# FuzzOfWar.net
KiCad netlist of a schematic drawn in EAGLE
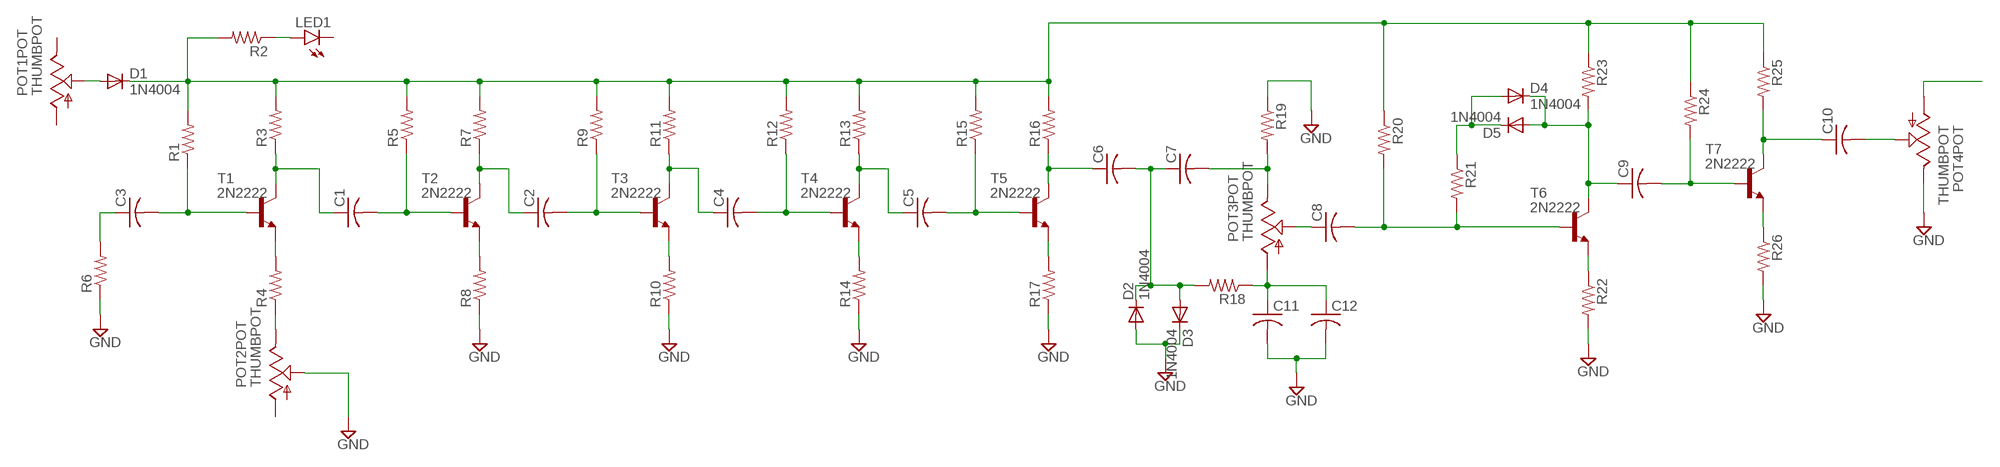
[diagram p0: schematic, sheet 1]

(export (version "E")
  (design (tool "Eeschema 10.0.6"))
  (components
    (comp (ref "C1")
      (value "C-USC0603")
      (footprint "eagle-import:C0603")
      (libsource (lib "eagle-import") (part "C-USC0603"))
    )
    (comp (ref "C2")
      (value "C-USC0603")
      (footprint "eagle-import:C0603")
      (libsource (lib "eagle-import") (part "C-USC0603"))
    )
    (comp (ref "C3")
      (value "C-USC0603")
      (footprint "eagle-import:C0603")
      (libsource (lib "eagle-import") (part "C-USC0603"))
    )
    (comp (ref "C4")
      (value "C-USC0603")
      (footprint "eagle-import:C0603")
      (libsource (lib "eagle-import") (part "C-USC0603"))
    )
    (comp (ref "C5")
      (value "C-USC0603")
      (footprint "eagle-import:C0603")
      (libsource (lib "eagle-import") (part "C-USC0603"))
    )
    (comp (ref "C6")
      (value "C-USC0603")
      (footprint "eagle-import:C0603")
      (libsource (lib "eagle-import") (part "C-USC0603"))
    )
    (comp (ref "C7")
      (value "C-USC0603")
      (footprint "eagle-import:C0603")
      (libsource (lib "eagle-import") (part "C-USC0603"))
    )
    (comp (ref "C8")
      (value "C-USC0603")
      (footprint "eagle-import:C0603")
      (libsource (lib "eagle-import") (part "C-USC0603"))
    )
    (comp (ref "C9")
      (value "C-USC0603")
      (footprint "eagle-import:C0603")
      (libsource (lib "eagle-import") (part "C-USC0603"))
    )
    (comp (ref "C10")
      (value "C-USC0603")
      (footprint "eagle-import:C0603")
      (libsource (lib "eagle-import") (part "C-USC0603"))
    )
    (comp (ref "C11")
      (value "C-USC0603")
      (footprint "eagle-import:C0603")
      (libsource (lib "eagle-import") (part "C-USC0603"))
    )
    (comp (ref "C12")
      (value "C-USC0603")
      (footprint "eagle-import:C0603")
      (libsource (lib "eagle-import") (part "C-USC0603"))
    )
    (comp (ref "D1")
      (value "1N4004")
      (footprint "eagle-import:DO41-10")
      (libsource (lib "eagle-import") (part "1N4004"))
    )
    (comp (ref "D2")
      (value "1N4004")
      (footprint "eagle-import:DO41-10")
      (libsource (lib "eagle-import") (part "1N4004"))
    )
    (comp (ref "D3")
      (value "1N4004")
      (footprint "eagle-import:DO41-10")
      (libsource (lib "eagle-import") (part "1N4004"))
    )
    (comp (ref "D4")
      (value "1N4004")
      (footprint "eagle-import:DO41-10")
      (libsource (lib "eagle-import") (part "1N4004"))
    )
    (comp (ref "D5")
      (value "1N4004")
      (footprint "eagle-import:DO41-10")
      (libsource (lib "eagle-import") (part "1N4004"))
    )
    (comp (ref "LED1")
      (value "LED3MM")
      (footprint "eagle-import:LED3MM")
      (libsource (lib "eagle-import") (part "LED3MM"))
    )
    (comp (ref "POT1")
      (value "THUMBPOT")
      (footprint "eagle-import:THUMBWHEEL")
      (libsource (lib "eagle-import") (part "THUMBPOT"))
    )
    (comp (ref "POT2")
      (value "THUMBPOT")
      (footprint "eagle-import:THUMBWHEEL")
      (libsource (lib "eagle-import") (part "THUMBPOT"))
    )
    (comp (ref "POT3")
      (value "THUMBPOT")
      (footprint "eagle-import:THUMBWHEEL")
      (libsource (lib "eagle-import") (part "THUMBPOT"))
    )
    (comp (ref "POT4")
      (value "THUMBPOT")
      (footprint "eagle-import:THUMBWHEEL")
      (libsource (lib "eagle-import") (part "THUMBPOT"))
    )
    (comp (ref "R1")
      (value "R-US_R0603")
      (footprint "eagle-import:R0603")
      (libsource (lib "eagle-import") (part "R-US_R0603"))
    )
    (comp (ref "R2")
      (value "R-US_R0603")
      (footprint "eagle-import:R0603")
      (libsource (lib "eagle-import") (part "R-US_R0603"))
    )
    (comp (ref "R3")
      (value "R-US_R0603")
      (footprint "eagle-import:R0603")
      (libsource (lib "eagle-import") (part "R-US_R0603"))
    )
    (comp (ref "R4")
      (value "R-US_R0603")
      (footprint "eagle-import:R0603")
      (libsource (lib "eagle-import") (part "R-US_R0603"))
    )
    (comp (ref "R5")
      (value "R-US_R0603")
      (footprint "eagle-import:R0603")
      (libsource (lib "eagle-import") (part "R-US_R0603"))
    )
    (comp (ref "R6")
      (value "R-US_R0603")
      (footprint "eagle-import:R0603")
      (libsource (lib "eagle-import") (part "R-US_R0603"))
    )
    (comp (ref "R7")
      (value "R-US_R0603")
      (footprint "eagle-import:R0603")
      (libsource (lib "eagle-import") (part "R-US_R0603"))
    )
    (comp (ref "R8")
      (value "R-US_R0603")
      (footprint "eagle-import:R0603")
      (libsource (lib "eagle-import") (part "R-US_R0603"))
    )
    (comp (ref "R9")
      (value "R-US_R0603")
      (footprint "eagle-import:R0603")
      (libsource (lib "eagle-import") (part "R-US_R0603"))
    )
    (comp (ref "R10")
      (value "R-US_R0603")
      (footprint "eagle-import:R0603")
      (libsource (lib "eagle-import") (part "R-US_R0603"))
    )
    (comp (ref "R11")
      (value "R-US_R0603")
      (footprint "eagle-import:R0603")
      (libsource (lib "eagle-import") (part "R-US_R0603"))
    )
    (comp (ref "R12")
      (value "R-US_R0603")
      (footprint "eagle-import:R0603")
      (libsource (lib "eagle-import") (part "R-US_R0603"))
    )
    (comp (ref "R13")
      (value "R-US_R0603")
      (footprint "eagle-import:R0603")
      (libsource (lib "eagle-import") (part "R-US_R0603"))
    )
    (comp (ref "R14")
      (value "R-US_R0603")
      (footprint "eagle-import:R0603")
      (libsource (lib "eagle-import") (part "R-US_R0603"))
    )
    (comp (ref "R15")
      (value "R-US_R0603")
      (footprint "eagle-import:R0603")
      (libsource (lib "eagle-import") (part "R-US_R0603"))
    )
    (comp (ref "R16")
      (value "R-US_R0603")
      (footprint "eagle-import:R0603")
      (libsource (lib "eagle-import") (part "R-US_R0603"))
    )
    (comp (ref "R17")
      (value "R-US_R0603")
      (footprint "eagle-import:R0603")
      (libsource (lib "eagle-import") (part "R-US_R0603"))
    )
    (comp (ref "R18")
      (value "R-US_R0603")
      (footprint "eagle-import:R0603")
      (libsource (lib "eagle-import") (part "R-US_R0603"))
    )
    (comp (ref "R19")
      (value "R-US_R0603")
      (footprint "eagle-import:R0603")
      (libsource (lib "eagle-import") (part "R-US_R0603"))
    )
    (comp (ref "R20")
      (value "R-US_R0603")
      (footprint "eagle-import:R0603")
      (libsource (lib "eagle-import") (part "R-US_R0603"))
    )
    (comp (ref "R21")
      (value "R-US_R0603")
      (footprint "eagle-import:R0603")
      (libsource (lib "eagle-import") (part "R-US_R0603"))
    )
    (comp (ref "R22")
      (value "R-US_R0603")
      (footprint "eagle-import:R0603")
      (libsource (lib "eagle-import") (part "R-US_R0603"))
    )
    (comp (ref "R23")
      (value "R-US_R0603")
      (footprint "eagle-import:R0603")
      (libsource (lib "eagle-import") (part "R-US_R0603"))
    )
    (comp (ref "R24")
      (value "R-US_R0603")
      (footprint "eagle-import:R0603")
      (libsource (lib "eagle-import") (part "R-US_R0603"))
    )
    (comp (ref "R25")
      (value "R-US_R0603")
      (footprint "eagle-import:R0603")
      (libsource (lib "eagle-import") (part "R-US_R0603"))
    )
    (comp (ref "R26")
      (value "R-US_R0603")
      (footprint "eagle-import:R0603")
      (libsource (lib "eagle-import") (part "R-US_R0603"))
    )
    (comp (ref "T1")
      (value "2N2222")
      (footprint "eagle-import:TO92-EBC-OVAL")
      (libsource (lib "eagle-import") (part "2N2222"))
    )
    (comp (ref "T2")
      (value "2N2222")
      (footprint "eagle-import:TO92-EBC-OVAL")
      (libsource (lib "eagle-import") (part "2N2222"))
    )
    (comp (ref "T3")
      (value "2N2222")
      (footprint "eagle-import:TO92-EBC-OVAL")
      (libsource (lib "eagle-import") (part "2N2222"))
    )
    (comp (ref "T4")
      (value "2N2222")
      (footprint "eagle-import:TO92-EBC-OVAL")
      (libsource (lib "eagle-import") (part "2N2222"))
    )
    (comp (ref "T5")
      (value "2N2222")
      (footprint "eagle-import:TO92-EBC-OVAL")
      (libsource (lib "eagle-import") (part "2N2222"))
    )
    (comp (ref "T6")
      (value "2N2222")
      (footprint "eagle-import:TO92-EBC-OVAL")
      (libsource (lib "eagle-import") (part "2N2222"))
    )
    (comp (ref "T7")
      (value "2N2222")
      (footprint "eagle-import:TO92-EBC-OVAL")
      (libsource (lib "eagle-import") (part "2N2222"))
    )
  )
  (nets
    (net (code "1") (name "GND") (class "Default")
      (node (ref "C11") (pin "2") (pinfunction "2_2") (pintype "passive"))
      (node (ref "C12") (pin "2") (pinfunction "2_2") (pintype "passive"))
      (node (ref "D2") (pin "A") (pinfunction "A_A") (pintype "passive"))
      (node (ref "D3") (pin "C") (pinfunction "C_C") (pintype "passive"))
      (node (ref "POT2") (pin "2") (pinfunction "S_2") (pintype "passive"))
      (node (ref "POT4") (pin "3") (pinfunction "E_3") (pintype "passive"))
      (node (ref "R10") (pin "1") (pinfunction "1_1") (pintype "passive"))
      (node (ref "R14") (pin "1") (pinfunction "1_1") (pintype "passive"))
      (node (ref "R17") (pin "1") (pinfunction "1_1") (pintype "passive"))
      (node (ref "R19") (pin "1") (pinfunction "1_1") (pintype "passive"))
      (node (ref "R22") (pin "2") (pinfunction "2_2") (pintype "passive"))
      (node (ref "R26") (pin "2") (pinfunction "2_2") (pintype "passive"))
      (node (ref "R6") (pin "1") (pinfunction "1_1") (pintype "passive"))
      (node (ref "R8") (pin "1") (pinfunction "1_1") (pintype "passive"))
    )
    (net (code "2") (name "Net-(C1-Pad1)") (class "Default")
      (node (ref "C1") (pin "1") (pinfunction "1_1") (pintype "passive"))
      (node (ref "R3") (pin "1") (pinfunction "1_1") (pintype "passive"))
      (node (ref "T1") (pin "C") (pinfunction "C_C") (pintype "passive"))
    )
    (net (code "3") (name "Net-(C1-Pad2)") (class "Default")
      (node (ref "C1") (pin "2") (pinfunction "2_2") (pintype "passive"))
      (node (ref "R5") (pin "1") (pinfunction "1_1") (pintype "passive"))
      (node (ref "T2") (pin "B") (pinfunction "B_B") (pintype "passive"))
    )
    (net (code "4") (name "Net-(C2-Pad1)") (class "Default")
      (node (ref "C2") (pin "1") (pinfunction "1_1") (pintype "passive"))
      (node (ref "R7") (pin "1") (pinfunction "1_1") (pintype "passive"))
      (node (ref "T2") (pin "C") (pinfunction "C_C") (pintype "passive"))
    )
    (net (code "5") (name "Net-(C2-Pad2)") (class "Default")
      (node (ref "C2") (pin "2") (pinfunction "2_2") (pintype "passive"))
      (node (ref "R9") (pin "1") (pinfunction "1_1") (pintype "passive"))
      (node (ref "T3") (pin "B") (pinfunction "B_B") (pintype "passive"))
    )
    (net (code "6") (name "Net-(C3-Pad1)") (class "Default")
      (node (ref "C3") (pin "1") (pinfunction "1_1") (pintype "passive"))
      (node (ref "R6") (pin "2") (pinfunction "2_2") (pintype "passive"))
    )
    (net (code "7") (name "Net-(C3-Pad2)") (class "Default")
      (node (ref "C3") (pin "2") (pinfunction "2_2") (pintype "passive"))
      (node (ref "R1") (pin "1") (pinfunction "1_1") (pintype "passive"))
      (node (ref "T1") (pin "B") (pinfunction "B_B") (pintype "passive"))
    )
    (net (code "8") (name "Net-(C4-Pad1)") (class "Default")
      (node (ref "C4") (pin "1") (pinfunction "1_1") (pintype "passive"))
      (node (ref "R11") (pin "1") (pinfunction "1_1") (pintype "passive"))
      (node (ref "T3") (pin "C") (pinfunction "C_C") (pintype "passive"))
    )
    (net (code "9") (name "Net-(C4-Pad2)") (class "Default")
      (node (ref "C4") (pin "2") (pinfunction "2_2") (pintype "passive"))
      (node (ref "R12") (pin "1") (pinfunction "1_1") (pintype "passive"))
      (node (ref "T4") (pin "B") (pinfunction "B_B") (pintype "passive"))
    )
    (net (code "10") (name "Net-(C5-Pad1)") (class "Default")
      (node (ref "C5") (pin "1") (pinfunction "1_1") (pintype "passive"))
      (node (ref "R13") (pin "1") (pinfunction "1_1") (pintype "passive"))
      (node (ref "T4") (pin "C") (pinfunction "C_C") (pintype "passive"))
    )
    (net (code "11") (name "Net-(C5-Pad2)") (class "Default")
      (node (ref "C5") (pin "2") (pinfunction "2_2") (pintype "passive"))
      (node (ref "R15") (pin "1") (pinfunction "1_1") (pintype "passive"))
      (node (ref "T5") (pin "B") (pinfunction "B_B") (pintype "passive"))
    )
    (net (code "12") (name "Net-(C6-Pad1)") (class "Default")
      (node (ref "C6") (pin "1") (pinfunction "1_1") (pintype "passive"))
      (node (ref "R16") (pin "1") (pinfunction "1_1") (pintype "passive"))
      (node (ref "T5") (pin "C") (pinfunction "C_C") (pintype "passive"))
    )
    (net (code "13") (name "Net-(C6-Pad2)") (class "Default")
      (node (ref "C6") (pin "2") (pinfunction "2_2") (pintype "passive"))
      (node (ref "C7") (pin "1") (pinfunction "1_1") (pintype "passive"))
      (node (ref "D2") (pin "C") (pinfunction "C_C") (pintype "passive"))
      (node (ref "D3") (pin "A") (pinfunction "A_A") (pintype "passive"))
      (node (ref "R18") (pin "2") (pinfunction "2_2") (pintype "passive"))
    )
    (net (code "14") (name "Net-(C8-Pad2)") (class "Default")
      (node (ref "C8") (pin "2") (pinfunction "2_2") (pintype "passive"))
      (node (ref "R20") (pin "2") (pinfunction "2_2") (pintype "passive"))
      (node (ref "R21") (pin "2") (pinfunction "2_2") (pintype "passive"))
      (node (ref "T6") (pin "B") (pinfunction "B_B") (pintype "passive"))
    )
    (net (code "15") (name "Net-(C9-Pad1)") (class "Default")
      (node (ref "C9") (pin "1") (pinfunction "1_1") (pintype "passive"))
      (node (ref "D4") (pin "C") (pinfunction "C_C") (pintype "passive"))
      (node (ref "D5") (pin "A") (pinfunction "A_A") (pintype "passive"))
      (node (ref "R23") (pin "2") (pinfunction "2_2") (pintype "passive"))
      (node (ref "T6") (pin "C") (pinfunction "C_C") (pintype "passive"))
    )
    (net (code "16") (name "Net-(C9-Pad2)") (class "Default")
      (node (ref "C9") (pin "2") (pinfunction "2_2") (pintype "passive"))
      (node (ref "R24") (pin "2") (pinfunction "2_2") (pintype "passive"))
      (node (ref "T7") (pin "B") (pinfunction "B_B") (pintype "passive"))
    )
    (net (code "17") (name "Net-(C10-Pad1)") (class "Default")
      (node (ref "C10") (pin "1") (pinfunction "1_1") (pintype "passive"))
      (node (ref "R25") (pin "2") (pinfunction "2_2") (pintype "passive"))
      (node (ref "T7") (pin "C") (pinfunction "C_C") (pintype "passive"))
    )
    (net (code "18") (name "Net-(D1-PadC)") (class "Default")
      (node (ref "D1") (pin "C") (pinfunction "C_C") (pintype "passive"))
      (node (ref "R1") (pin "2") (pinfunction "2_2") (pintype "passive"))
      (node (ref "R11") (pin "2") (pinfunction "2_2") (pintype "passive"))
      (node (ref "R12") (pin "2") (pinfunction "2_2") (pintype "passive"))
      (node (ref "R13") (pin "2") (pinfunction "2_2") (pintype "passive"))
      (node (ref "R15") (pin "2") (pinfunction "2_2") (pintype "passive"))
      (node (ref "R16") (pin "2") (pinfunction "2_2") (pintype "passive"))
      (node (ref "R2") (pin "2") (pinfunction "2_2") (pintype "passive"))
      (node (ref "R20") (pin "1") (pinfunction "1_1") (pintype "passive"))
      (node (ref "R23") (pin "1") (pinfunction "1_1") (pintype "passive"))
      (node (ref "R24") (pin "1") (pinfunction "1_1") (pintype "passive"))
      (node (ref "R25") (pin "1") (pinfunction "1_1") (pintype "passive"))
      (node (ref "R3") (pin "2") (pinfunction "2_2") (pintype "passive"))
      (node (ref "R5") (pin "2") (pinfunction "2_2") (pintype "passive"))
      (node (ref "R7") (pin "2") (pinfunction "2_2") (pintype "passive"))
      (node (ref "R9") (pin "2") (pinfunction "2_2") (pintype "passive"))
    )
    (net (code "19") (name "Net-(D4-PadA)") (class "Default")
      (node (ref "D4") (pin "A") (pinfunction "A_A") (pintype "passive"))
      (node (ref "D5") (pin "C") (pinfunction "C_C") (pintype "passive"))
      (node (ref "R21") (pin "1") (pinfunction "1_1") (pintype "passive"))
    )
    (net (code "20") (name "Net-(LED1-PadA)") (class "Default")
      (node (ref "LED1") (pin "A") (pinfunction "A_A") (pintype "passive"))
      (node (ref "R2") (pin "1") (pinfunction "1_1") (pintype "passive"))
    )
    (net (code "21") (name "Net-(POT1A-S)") (class "Default")
      (node (ref "D1") (pin "A") (pinfunction "A_A") (pintype "passive"))
      (node (ref "POT1") (pin "2") (pinfunction "S_2") (pintype "passive"))
    )
    (net (code "22") (name "Net-(POT2A-E)") (class "Default")
      (node (ref "POT2") (pin "3") (pinfunction "E_3") (pintype "passive"))
      (node (ref "R4") (pin "1") (pinfunction "1_1") (pintype "passive"))
    )
    (net (code "23") (name "Net-(POT3A-A)") (class "Default")
      (node (ref "C11") (pin "1") (pinfunction "1_1") (pintype "passive"))
      (node (ref "C12") (pin "1") (pinfunction "1_1") (pintype "passive"))
      (node (ref "POT3") (pin "1") (pinfunction "A_1") (pintype "passive"))
      (node (ref "R18") (pin "1") (pinfunction "1_1") (pintype "passive"))
    )
    (net (code "24") (name "Net-(POT3A-E)") (class "Default")
      (node (ref "C7") (pin "2") (pinfunction "2_2") (pintype "passive"))
      (node (ref "POT3") (pin "3") (pinfunction "E_3") (pintype "passive"))
      (node (ref "R19") (pin "2") (pinfunction "2_2") (pintype "passive"))
    )
    (net (code "25") (name "Net-(POT3A-S)") (class "Default")
      (node (ref "C8") (pin "1") (pinfunction "1_1") (pintype "passive"))
      (node (ref "POT3") (pin "2") (pinfunction "S_2") (pintype "passive"))
    )
    (net (code "26") (name "Net-(POT4A-S)") (class "Default")
      (node (ref "C10") (pin "2") (pinfunction "2_2") (pintype "passive"))
      (node (ref "POT4") (pin "2") (pinfunction "S_2") (pintype "passive"))
    )
    (net (code "27") (name "Net-(R4-Pad2)") (class "Default")
      (node (ref "R4") (pin "2") (pinfunction "2_2") (pintype "passive"))
      (node (ref "T1") (pin "E") (pinfunction "E_E") (pintype "passive"))
    )
    (net (code "28") (name "Net-(R8-Pad2)") (class "Default")
      (node (ref "R8") (pin "2") (pinfunction "2_2") (pintype "passive"))
      (node (ref "T2") (pin "E") (pinfunction "E_E") (pintype "passive"))
    )
    (net (code "29") (name "Net-(R10-Pad2)") (class "Default")
      (node (ref "R10") (pin "2") (pinfunction "2_2") (pintype "passive"))
      (node (ref "T3") (pin "E") (pinfunction "E_E") (pintype "passive"))
    )
    (net (code "30") (name "Net-(R14-Pad2)") (class "Default")
      (node (ref "R14") (pin "2") (pinfunction "2_2") (pintype "passive"))
      (node (ref "T4") (pin "E") (pinfunction "E_E") (pintype "passive"))
    )
    (net (code "31") (name "Net-(R17-Pad2)") (class "Default")
      (node (ref "R17") (pin "2") (pinfunction "2_2") (pintype "passive"))
      (node (ref "T5") (pin "E") (pinfunction "E_E") (pintype "passive"))
    )
    (net (code "32") (name "Net-(R22-Pad1)") (class "Default")
      (node (ref "R22") (pin "1") (pinfunction "1_1") (pintype "passive"))
      (node (ref "T6") (pin "E") (pinfunction "E_E") (pintype "passive"))
    )
    (net (code "33") (name "Net-(R26-Pad1)") (class "Default")
      (node (ref "R26") (pin "1") (pinfunction "1_1") (pintype "passive"))
      (node (ref "T7") (pin "E") (pinfunction "E_E") (pintype "passive"))
    )
    (net (code "34") (name "unconnected-(LED1-C-PadK)") (class "Default")
      (node (ref "LED1") (pin "K") (pinfunction "C_K") (pintype "passive"))
    )
    (net (code "35") (name "unconnected-(POT1A-A-Pad1)") (class "Default")
      (node (ref "POT1") (pin "1") (pinfunction "A_1") (pintype "passive"))
    )
    (net (code "36") (name "unconnected-(POT1A-E-Pad3)") (class "Default")
      (node (ref "POT1") (pin "3") (pinfunction "E_3") (pintype "passive"))
    )
    (net (code "37") (name "unconnected-(POT2A-A-Pad1)") (class "Default")
      (node (ref "POT2") (pin "1") (pinfunction "A_1") (pintype "passive"))
    )
    (net (code "38") (name "unconnected-(POT4A-A-Pad1)") (class "Default")
      (node (ref "POT4") (pin "1") (pinfunction "A_1") (pintype "passive"))
    )
  )
)
